# TPL-transceiver.net
KiCad netlist of a schematic drawn in Altium Designer
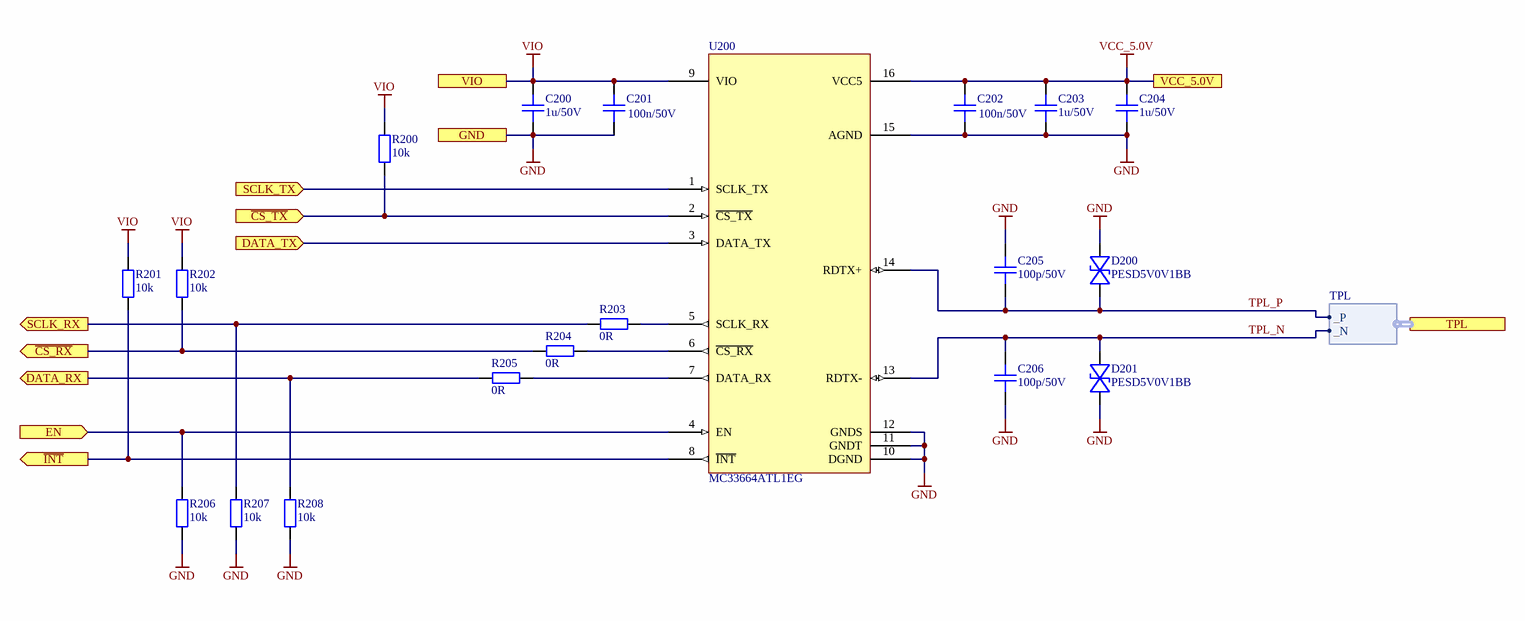
[diagram p0: TPL-transceiver.SchDoc]

(export (version "E")
  (design (tool "Eeschema 10.0.6"))
  (components
    (comp (ref "C200")
      (value "1u/50V")
      (footprint "CAPC2012X14N")
      (description "MLCC")
      (fields (field (name "PART NUMBER") "gen_C_ceramic_1u_50V_X7R_0805") (field (name "TOLERANCE") "± 10%"))
      (libsource (lib "OE750") (part "C"))
    )
    (comp (ref "C201")
      (value "100n/50V")
      (footprint "CAPC1608X08N")
      (description "MLCC")
      (fields (field (name "PART NUMBER") "gen_C_ceramic_100n_50V_X7R_0603"))
      (libsource (lib "OE750") (part "C"))
    )
    (comp (ref "C202")
      (value "100n/50V")
      (footprint "CAPC1608X08N")
      (description "MLCC")
      (fields (field (name "PART NUMBER") "gen_C_ceramic_100n_50V_X7R_0603"))
      (libsource (lib "OE750") (part "C"))
    )
    (comp (ref "C203")
      (value "1u/50V")
      (footprint "CAPC2012X14N")
      (description "MLCC")
      (fields (field (name "PART NUMBER") "gen_C_ceramic_1u_50V_X7R_0805") (field (name "TOLERANCE") "± 10%"))
      (libsource (lib "OE750") (part "C"))
    )
    (comp (ref "C204")
      (value "1u/50V")
      (footprint "CAPC2012X14N")
      (description "MLCC")
      (fields (field (name "PART NUMBER") "gen_C_ceramic_1u_50V_X7R_0805") (field (name "TOLERANCE") "± 10%"))
      (libsource (lib "OE750") (part "C"))
    )
    (comp (ref "C205")
      (value "100p/50V")
      (footprint "CAPC1608X08N")
      (description "MLCC")
      (fields
        (field (name "PART NUMBER") "gen_C_ceramic_100p_50V_C0G_0603")
        (field (name "TOLERANCE") "± 10%")
      )
      (libsource (lib "OE750") (part "C"))
    )
    (comp (ref "C206")
      (value "100p/50V")
      (footprint "CAPC1608X08N")
      (description "MLCC")
      (fields
        (field (name "PART NUMBER") "gen_C_ceramic_100p_50V_C0G_0603")
        (field (name "TOLERANCE") "± 10%")
      )
      (libsource (lib "OE750") (part "C"))
    )
    (comp (ref "D200")
      (value "PESD5V0V1BB")
      (footprint "SOD523_PESD_NEXPERIA")
      (description "Very low capacitance bidirectional ESD protection diode")
      (fields (field (name "MANUFACTURER") "Nexperia"))
      (libsource (lib "OE750") (part "D_TVS_bi"))
    )
    (comp (ref "D201")
      (value "PESD5V0V1BB")
      (footprint "SOD523_PESD_NEXPERIA")
      (description "Very low capacitance bidirectional ESD protection diode")
      (fields (field (name "MANUFACTURER") "Nexperia"))
      (libsource (lib "OE750") (part "D_TVS_bi"))
    )
    (comp (ref "R200")
      (value "10k")
      (footprint "RESC1608X05N")
      (description "SMD Resistor 10k 0603")
      (fields (field (name "PART NUMBER") "gen_R_10k_0603") (field (name "TOLERANCE") "1%"))
      (libsource (lib "OE750") (part "R"))
    )
    (comp (ref "R201")
      (value "10k")
      (footprint "RESC1608X05N")
      (description "SMD Resistor 10k 0603")
      (fields (field (name "PART NUMBER") "gen_R_10k_0603") (field (name "TOLERANCE") "1%"))
      (libsource (lib "OE750") (part "R"))
    )
    (comp (ref "R202")
      (value "10k")
      (footprint "RESC1608X05N")
      (description "SMD Resistor 10k 0603")
      (fields (field (name "PART NUMBER") "gen_R_10k_0603") (field (name "TOLERANCE") "1%"))
      (libsource (lib "OE750") (part "R"))
    )
    (comp (ref "R203")
      (value "0R")
      (footprint "RESC1608X05N")
      (description "SMD Resistor 0R 0603")
      (fields (field (name "PART NUMBER") "gen_R_0R_0603") (field (name "POWER") "0.1W"))
      (libsource (lib "OE750") (part "R"))
    )
    (comp (ref "R204")
      (value "0R")
      (footprint "RESC1608X05N")
      (description "SMD Resistor 0R 0603")
      (fields (field (name "PART NUMBER") "gen_R_0R_0603") (field (name "POWER") "0.1W"))
      (libsource (lib "OE750") (part "R"))
    )
    (comp (ref "R205")
      (value "0R")
      (footprint "RESC1608X05N")
      (description "SMD Resistor 0R 0603")
      (fields (field (name "PART NUMBER") "gen_R_0R_0603") (field (name "POWER") "0.1W"))
      (libsource (lib "OE750") (part "R"))
    )
    (comp (ref "R206")
      (value "10k")
      (footprint "RESC1608X05N")
      (description "SMD Resistor 10k 0603")
      (fields (field (name "PART NUMBER") "gen_R_10k_0603") (field (name "TOLERANCE") "1%"))
      (libsource (lib "OE750") (part "R"))
    )
    (comp (ref "R207")
      (value "10k")
      (footprint "RESC1608X05N")
      (description "SMD Resistor 10k 0603")
      (fields (field (name "PART NUMBER") "gen_R_10k_0603") (field (name "TOLERANCE") "1%"))
      (libsource (lib "OE750") (part "R"))
    )
    (comp (ref "R208")
      (value "10k")
      (footprint "RESC1608X05N")
      (description "SMD Resistor 10k 0603")
      (fields (field (name "PART NUMBER") "gen_R_10k_0603") (field (name "TOLERANCE") "1%"))
      (libsource (lib "OE750") (part "R"))
    )
    (comp (ref "U200")
      (value "MC33664ATL1EG")
      (footprint "MC33664ATL1EG")
      (description "Isolated network high-speed transceiver")
      (fields (field (name "MANUFACTURER") "NXP"))
      (libsource (lib "OE750") (part "MC33664"))
    )
  )
  (nets
    (net (code "2") (name "/CS_RX") (class "Default")
      (node (ref "R202") (pin "1") (pinfunction "1_1") (pintype "passive"))
      (node (ref "R204") (pin "1") (pinfunction "1_1") (pintype "passive"))
    )
    (net (code "3") (name "/CS_TX") (class "Default")
      (node (ref "R200") (pin "1") (pinfunction "1_1") (pintype "passive"))
      (node (ref "U200") (pin "2") (pinfunction "CS_TX_2") (pintype "input"))
    )
    (net (code "4") (name "/DATA_RX") (class "Default")
      (node (ref "R205") (pin "1") (pinfunction "1_1") (pintype "passive"))
      (node (ref "R208") (pin "2") (pinfunction "2_2") (pintype "passive"))
    )
    (net (code "5") (name "/DATA_TX") (class "Default")
      (node (ref "U200") (pin "3") (pinfunction "DATA_TX_3") (pintype "input"))
    )
    (net (code "6") (name "/EN") (class "Default")
      (node (ref "R206") (pin "2") (pinfunction "2_2") (pintype "passive"))
      (node (ref "U200") (pin "4") (pinfunction "EN_4") (pintype "input"))
    )
    (net (code "7") (name "/INT") (class "Default")
      (node (ref "R201") (pin "1") (pinfunction "1_1") (pintype "passive"))
      (node (ref "U200") (pin "8") (pinfunction "INT_8") (pintype "output"))
    )
    (net (code "8") (name "/SCLK_RX") (class "Default")
      (node (ref "R203") (pin "1") (pinfunction "1_1") (pintype "passive"))
      (node (ref "R207") (pin "2") (pinfunction "2_2") (pintype "passive"))
    )
    (net (code "9") (name "/SCLK_TX") (class "Default")
      (node (ref "U200") (pin "1") (pinfunction "SCLK_TX_1") (pintype "input"))
    )
    (net (code "10") (name "/TPL_N") (class "Default")
      (node (ref "C206") (pin "2") (pinfunction "2_2") (pintype "passive"))
      (node (ref "D201") (pin "1") (pinfunction "C_1") (pintype "passive"))
      (node (ref "U200") (pin "13") (pinfunction "RDTX-_13") (pintype "bidirectional"))
    )
    (net (code "11") (name "/TPL_P") (class "Default")
      (node (ref "C205") (pin "1") (pinfunction "1_1") (pintype "passive"))
      (node (ref "D200") (pin "2") (pinfunction "A_2") (pintype "passive"))
      (node (ref "U200") (pin "14") (pinfunction "RDTX+_14") (pintype "bidirectional"))
    )
    (net (code "13") (name "GND") (class "Default")
      (node (ref "C200") (pin "1") (pinfunction "1_1") (pintype "passive"))
      (node (ref "C201") (pin "1") (pinfunction "1_1") (pintype "passive"))
      (node (ref "C202") (pin "1") (pinfunction "1_1") (pintype "passive"))
      (node (ref "C203") (pin "1") (pinfunction "1_1") (pintype "passive"))
      (node (ref "C204") (pin "1") (pinfunction "1_1") (pintype "passive"))
      (node (ref "C205") (pin "2") (pinfunction "2_2") (pintype "passive"))
      (node (ref "C206") (pin "1") (pinfunction "1_1") (pintype "passive"))
      (node (ref "D200") (pin "1") (pinfunction "C_1") (pintype "passive"))
      (node (ref "D201") (pin "2") (pinfunction "A_2") (pintype "passive"))
      (node (ref "R206") (pin "1") (pinfunction "1_1") (pintype "passive"))
      (node (ref "R207") (pin "1") (pinfunction "1_1") (pintype "passive"))
      (node (ref "R208") (pin "1") (pinfunction "1_1") (pintype "passive"))
      (node (ref "U200") (pin "10") (pinfunction "DGND_10") (pintype "power_in"))
      (node (ref "U200") (pin "11") (pinfunction "GNDT_11") (pintype "power_in"))
      (node (ref "U200") (pin "12") (pinfunction "GNDS_12") (pintype "power_in"))
      (node (ref "U200") (pin "15") (pinfunction "AGND_15") (pintype "power_in"))
    )
    (net (code "14") (name "Net-(U200-CS_RX)") (class "Default")
      (node (ref "R204") (pin "2") (pinfunction "2_2") (pintype "passive"))
      (node (ref "U200") (pin "6") (pinfunction "CS_RX_6") (pintype "output"))
    )
    (net (code "15") (name "Net-(U200-DATA_RX)") (class "Default")
      (node (ref "R205") (pin "2") (pinfunction "2_2") (pintype "passive"))
      (node (ref "U200") (pin "7") (pinfunction "DATA_RX_7") (pintype "output"))
    )
    (net (code "16") (name "Net-(U200-SCLK_RX)") (class "Default")
      (node (ref "R203") (pin "2") (pinfunction "2_2") (pintype "passive"))
      (node (ref "U200") (pin "5") (pinfunction "SCLK_RX_5") (pintype "output"))
    )
    (net (code "17") (name "VCC_5.0V") (class "Default")
      (node (ref "C202") (pin "2") (pinfunction "2_2") (pintype "passive"))
      (node (ref "C203") (pin "2") (pinfunction "2_2") (pintype "passive"))
      (node (ref "C204") (pin "2") (pinfunction "2_2") (pintype "passive"))
      (node (ref "U200") (pin "16") (pinfunction "VCC5_16") (pintype "power_in"))
    )
    (net (code "18") (name "VIO") (class "Default")
      (node (ref "C200") (pin "2") (pinfunction "2_2") (pintype "passive"))
      (node (ref "C201") (pin "2") (pinfunction "2_2") (pintype "passive"))
      (node (ref "R200") (pin "2") (pinfunction "2_2") (pintype "passive"))
      (node (ref "R201") (pin "2") (pinfunction "2_2") (pintype "passive"))
      (node (ref "R202") (pin "2") (pinfunction "2_2") (pintype "passive"))
      (node (ref "U200") (pin "9") (pinfunction "VIO_9") (pintype "power_in"))
    )
  )
)
